# Lipo_Charger_5v.net
KiCad netlist of a schematic drawn in EasyEDA
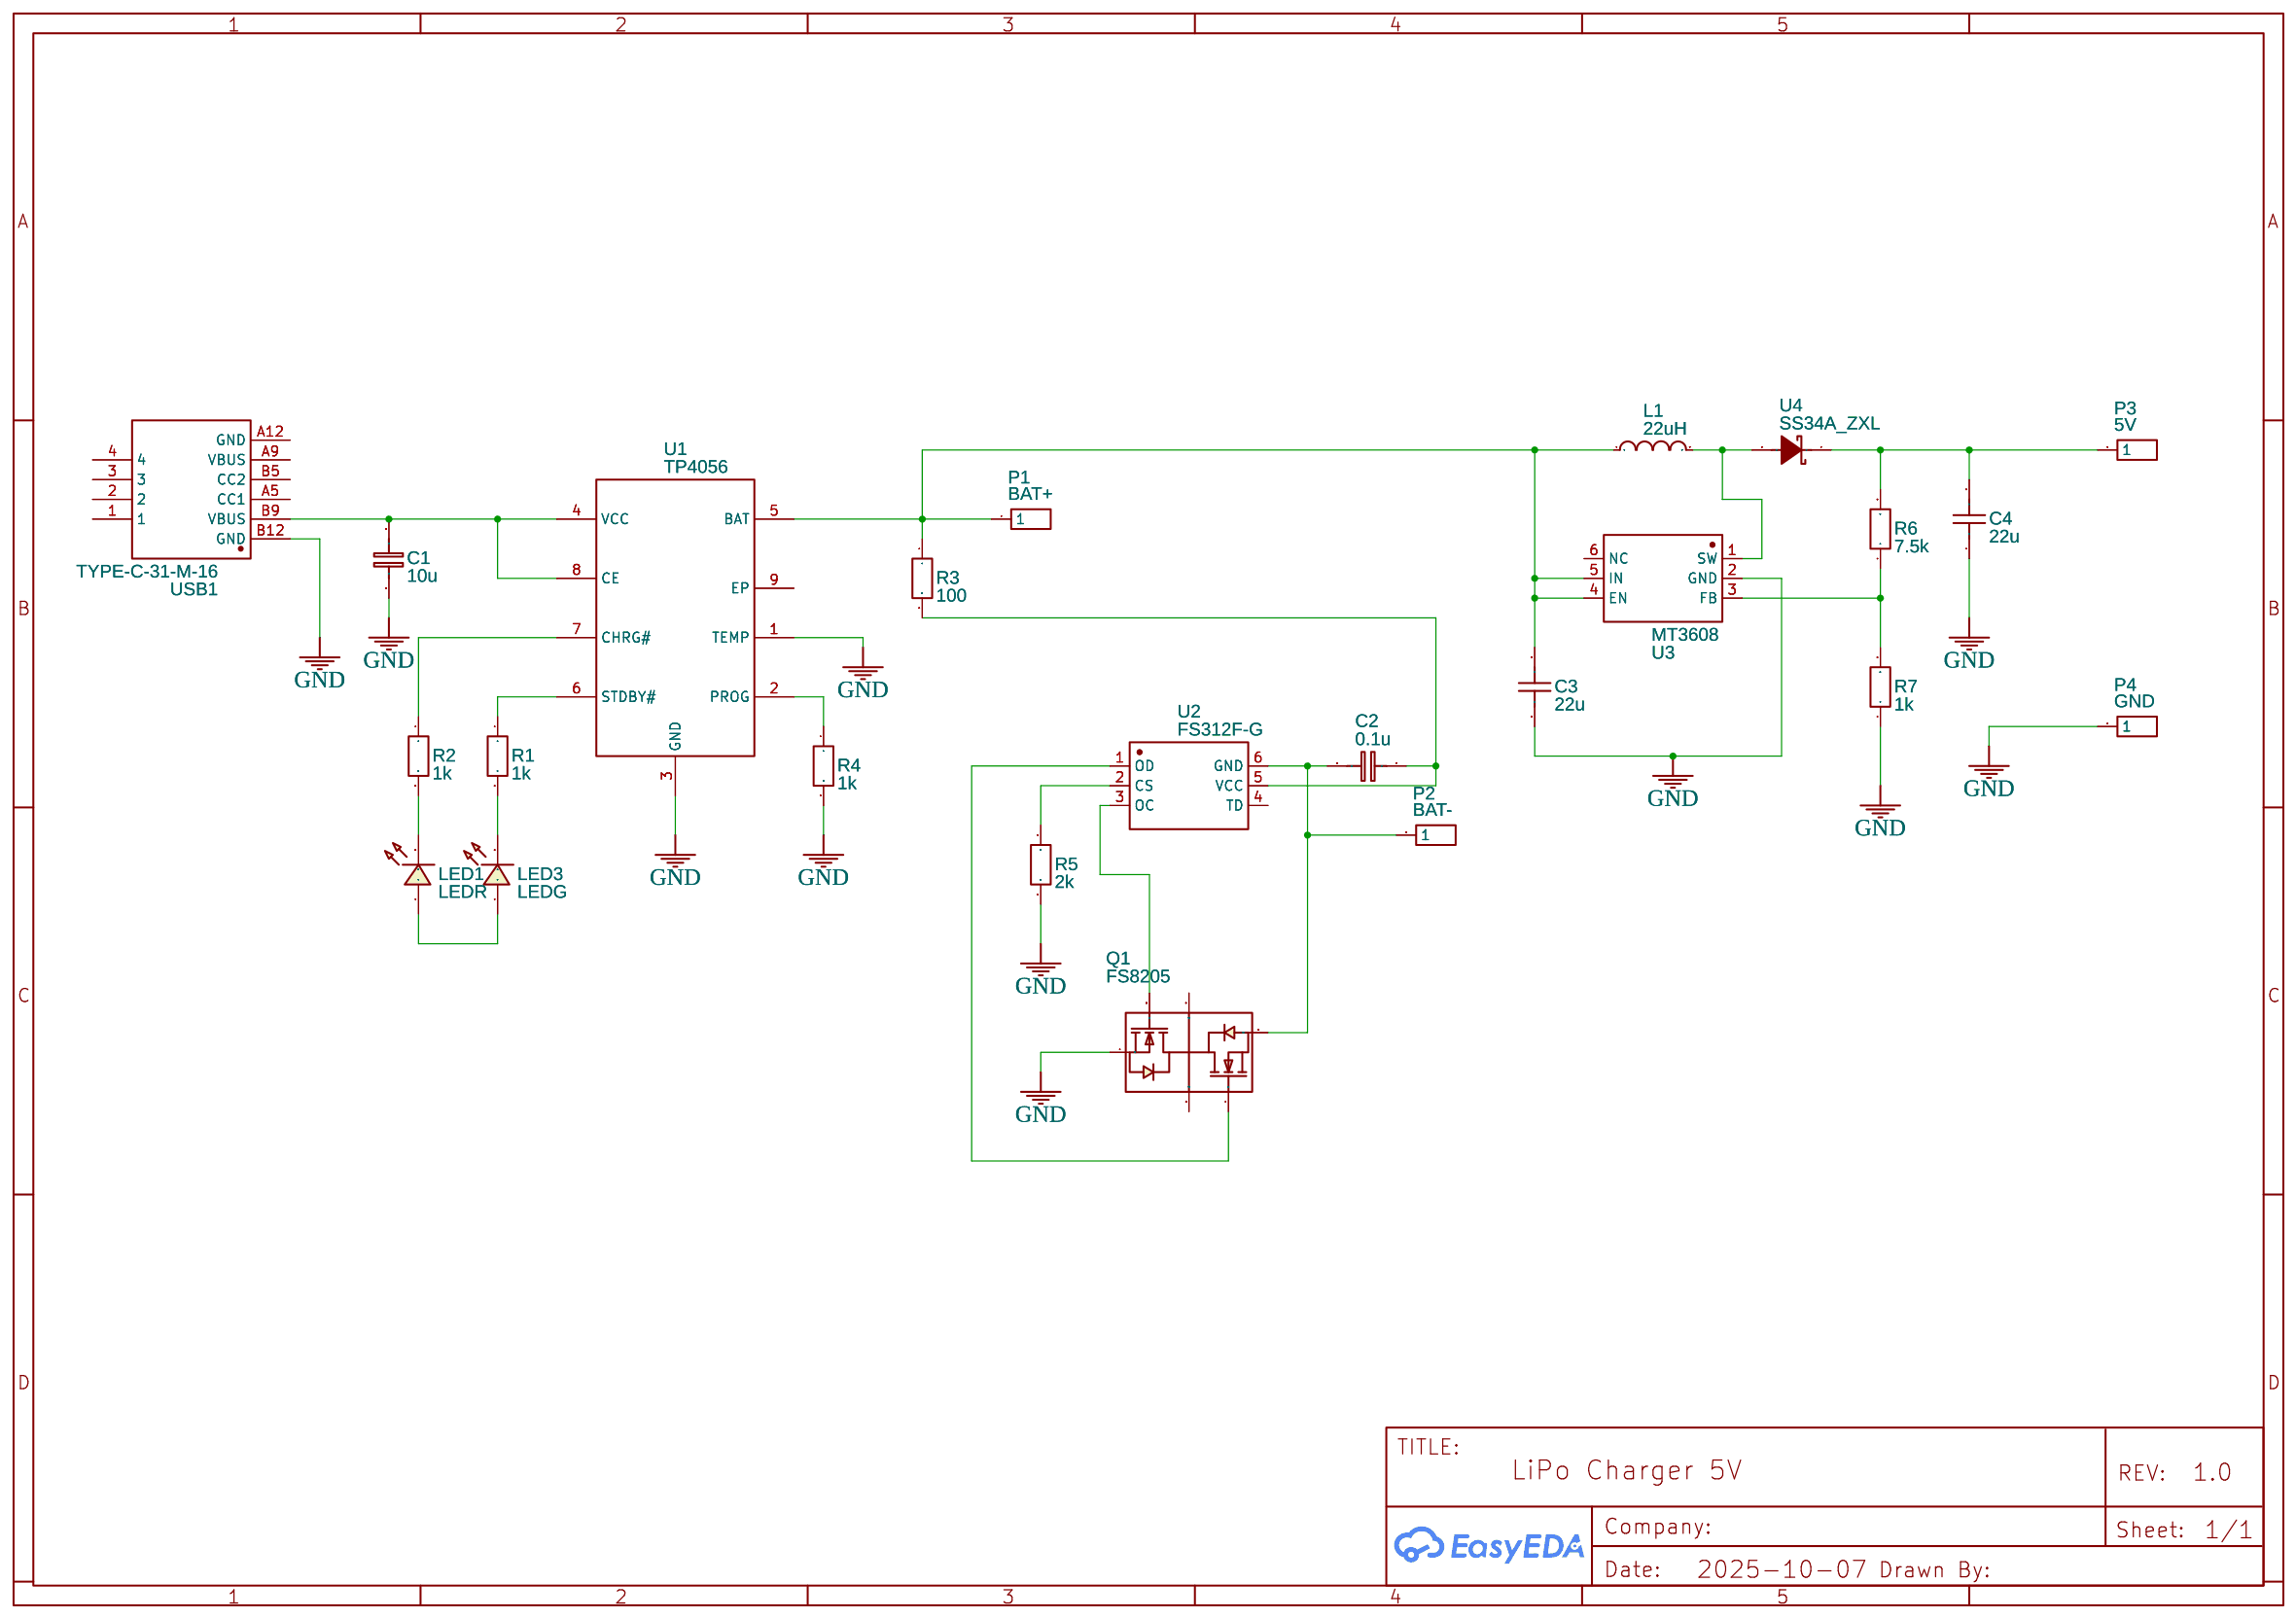
[diagram p0: schematic sheet]

(export (version "E")
  (design (tool "Eeschema 10.0.6"))
  (components
    (comp (ref "C1") (value "10u") (libsource (lib "") (part "C_0603_EU")))
    (comp (ref "C2") (value "0.1u") (libsource (lib "") (part "C_0603_EU_1")))
    (comp (ref "C3") (value "22u") (libsource (lib "") (part "C_0603_US")))
    (comp (ref "C4") (value "22u") (libsource (lib "") (part "C_0603_US")))
    (comp (ref "L1") (value "22uH") (libsource (lib "") (part "L0603_US")))
    (comp (ref "LED1")
      (value "LEDR")
      (fields
        (field (name "Manufacturer Part") "19-217/R6C-AL1M2VY/3T")
        (field (name "Manufacturer") "EVERLIGHT(台湾亿光)")
      )
      (libsource (lib "") (part "LED-0603_R"))
    )
    (comp (ref "LED3")
      (value "LEDG")
      (fields
        (field (name "Manufacturer Part") "19-217/GHC-YR1S2/3T")
        (field (name "Manufacturer") "EVERLIGHT(台湾亿光)")
      )
      (libsource (lib "") (part "LED-0603_G"))
    )
    (comp (ref "P1")
      (value "BAT+")
      (fields (field (name "Manufacturer Part") "2.54-1*1P针") (field (name "Manufacturer") "BOOMELE(博穆精密)"))
      (libsource (lib "") (part "Header-Male-2.54_1x1"))
    )
    (comp (ref "P2")
      (value "BAT-")
      (fields (field (name "Manufacturer Part") "2.54-1*1P针") (field (name "Manufacturer") "BOOMELE(博穆精密)"))
      (libsource (lib "") (part "Header-Male-2.54_1x1"))
    )
    (comp (ref "P3")
      (value "5V")
      (fields (field (name "Manufacturer Part") "2.54-1*1P针") (field (name "Manufacturer") "BOOMELE(博穆精密)"))
      (libsource (lib "") (part "Header-Male-2.54_1x1"))
    )
    (comp (ref "P4")
      (value "GND")
      (fields (field (name "Manufacturer Part") "2.54-1*1P针") (field (name "Manufacturer") "BOOMELE(博穆精密)"))
      (libsource (lib "") (part "Header-Male-2.54_1x1"))
    )
    (comp (ref "Q1")
      (value "FS8205")
      (fields (field (name "Manufacturer") "FORTUNE(富晶)"))
      (libsource (lib "") (part "FS8205"))
    )
    (comp (ref "R1") (value "1k") (libsource (lib "") (part "R_0603_EU")))
    (comp (ref "R2") (value "1k") (libsource (lib "") (part "R_0603_EU")))
    (comp (ref "R3") (value "100") (libsource (lib "") (part "R_0603_EU")))
    (comp (ref "R4") (value "1k") (libsource (lib "") (part "R_0603_EU")))
    (comp (ref "R5") (value "2k") (libsource (lib "") (part "R_0603_EU")))
    (comp (ref "R6") (value "7.5k") (libsource (lib "") (part "R_0603_EU_1")))
    (comp (ref "R7") (value "1k") (libsource (lib "") (part "R_0603_EU_1")))
    (comp (ref "U1")
      (value "TP4056")
      (fields
        (field (name "Manufacturer Part") "TP4056-42-ESOP8")
        (field (name "Manufacturer") "TOPPOWER(南京拓微)")
      )
      (libsource (lib "") (part "TP4056"))
    )
    (comp (ref "U2")
      (value "FS312F-G")
      (fields (field (name "Manufacturer") "FORTUNE(富晶)"))
      (libsource (lib "") (part "FS312F-G"))
    )
    (comp (ref "U3")
      (value "MT3608")
      (fields (field (name "Manufacturer") "西安航天民芯"))
      (libsource (lib "") (part "MT3608"))
    )
    (comp (ref "U4")
      (value "SS34A_ZXL")
      (fields (field (name "Manufacturer Part") "SS34A") (field (name "Manufacturer") "Zhengxin(正芯)"))
      (libsource (lib "") (part "SS34A_ZXL"))
    )
    (comp (ref "USB1")
      (value "TYPE-C-31-M-16")
      (fields (field (name "Manufacturer") "韩国韩荣"))
      (libsource (lib "") (part "TYPE-C-31-M-16"))
    )
  )
  (nets
    (net (code "1") (name "GND") (class "Default")
      (node (ref "C1") (pin "1") (pinfunction "1_1") (pintype "unspecified"))
      (node (ref "C3") (pin "1") (pinfunction "1_1") (pintype "unspecified"))
      (node (ref "C4") (pin "1") (pinfunction "1_1") (pintype "unspecified"))
      (node (ref "P4") (pin "1") (pinfunction "1_1") (pintype "input"))
      (node (ref "Q1") (pin "1") (pinfunction "S1_1") (pintype "unspecified"))
      (node (ref "R4") (pin "2") (pinfunction "2_2") (pintype "unspecified"))
      (node (ref "R5") (pin "2") (pinfunction "2_2") (pintype "unspecified"))
      (node (ref "R7") (pin "1") (pinfunction "1_1") (pintype "unspecified"))
      (node (ref "U1") (pin "1") (pinfunction "TEMP_1") (pintype "unspecified"))
      (node (ref "U1") (pin "3") (pinfunction "GND_3") (pintype "unspecified"))
      (node (ref "U3") (pin "2") (pinfunction "GND_2") (pintype "unspecified"))
      (node (ref "USB1") (pin "B12") (pinfunction "GND_B12") (pintype "unspecified"))
    )
    (net (code "2") (name "Net-(LED1-Pad1)") (class "Default")
      (node (ref "LED1") (pin "1") (pinfunction "1_1") (pintype "unspecified"))
      (node (ref "LED3") (pin "1") (pinfunction "1_1") (pintype "unspecified"))
    )
    (net (code "3") (name "Net-(LED1-Pad2)") (class "Default")
      (node (ref "LED1") (pin "2") (pinfunction "2_2") (pintype "unspecified"))
      (node (ref "R2") (pin "2") (pinfunction "2_2") (pintype "unspecified"))
    )
    (net (code "4") (name "Net-(LED3-Pad2)") (class "Default")
      (node (ref "LED3") (pin "2") (pinfunction "2_2") (pintype "unspecified"))
      (node (ref "R1") (pin "2") (pinfunction "2_2") (pintype "unspecified"))
    )
    (net (code "5") (name "Net-(Q1-G1)") (class "Default")
      (node (ref "Q1") (pin "6") (pinfunction "G1_6") (pintype "unspecified"))
      (node (ref "U2") (pin "3") (pinfunction "OC_3") (pintype "unspecified"))
    )
    (net (code "6") (name "Net-(Q1-G2)") (class "Default")
      (node (ref "Q1") (pin "4") (pinfunction "G2_4") (pintype "unspecified"))
      (node (ref "U2") (pin "1") (pinfunction "OD_1") (pintype "unspecified"))
    )
    (net (code "7") (name "Net-(Q1-S2)") (class "Default")
      (node (ref "C2") (pin "2") (pinfunction "2_2") (pintype "unspecified"))
      (node (ref "P2") (pin "1") (pinfunction "1_1") (pintype "input"))
      (node (ref "Q1") (pin "3") (pinfunction "S2_3") (pintype "unspecified"))
      (node (ref "U2") (pin "6") (pinfunction "GND_6") (pintype "unspecified"))
    )
    (net (code "8") (name "Net-(U1-BAT)") (class "Default")
      (node (ref "C3") (pin "2") (pinfunction "2_2") (pintype "unspecified"))
      (node (ref "L1") (pin "1") (pinfunction "1_1") (pintype "unspecified"))
      (node (ref "P1") (pin "1") (pinfunction "1_1") (pintype "input"))
      (node (ref "R3") (pin "1") (pinfunction "1_1") (pintype "unspecified"))
      (node (ref "U1") (pin "5") (pinfunction "BAT_5") (pintype "unspecified"))
      (node (ref "U3") (pin "4") (pinfunction "EN_4") (pintype "unspecified"))
      (node (ref "U3") (pin "5") (pinfunction "IN_5") (pintype "unspecified"))
    )
    (net (code "9") (name "Net-(U1-CE)") (class "Default")
      (node (ref "C1") (pin "2") (pinfunction "2_2") (pintype "unspecified"))
      (node (ref "U1") (pin "4") (pinfunction "VCC_4") (pintype "unspecified"))
      (node (ref "U1") (pin "8") (pinfunction "CE_8") (pintype "unspecified"))
      (node (ref "USB1") (pin "B9") (pinfunction "VBUS_B9") (pintype "unspecified"))
    )
    (net (code "10") (name "Net-(U1-CHRG#)") (class "Default")
      (node (ref "R2") (pin "1") (pinfunction "1_1") (pintype "unspecified"))
      (node (ref "U1") (pin "7") (pinfunction "CHRG#_7") (pintype "unspecified"))
    )
    (net (code "11") (name "Net-(U1-PROG)") (class "Default")
      (node (ref "R4") (pin "1") (pinfunction "1_1") (pintype "unspecified"))
      (node (ref "U1") (pin "2") (pinfunction "PROG_2") (pintype "unspecified"))
    )
    (net (code "12") (name "Net-(U1-STDBY#)") (class "Default")
      (node (ref "R1") (pin "1") (pinfunction "1_1") (pintype "unspecified"))
      (node (ref "U1") (pin "6") (pinfunction "STDBY#_6") (pintype "unspecified"))
    )
    (net (code "13") (name "Net-(U2-CS)") (class "Default")
      (node (ref "R5") (pin "1") (pinfunction "1_1") (pintype "unspecified"))
      (node (ref "U2") (pin "2") (pinfunction "CS_2") (pintype "unspecified"))
    )
    (net (code "14") (name "Net-(U2-VCC)") (class "Default")
      (node (ref "C2") (pin "1") (pinfunction "1_1") (pintype "unspecified"))
      (node (ref "R3") (pin "2") (pinfunction "2_2") (pintype "unspecified"))
      (node (ref "U2") (pin "5") (pinfunction "VCC_5") (pintype "unspecified"))
    )
    (net (code "15") (name "Net-(U3-FB)") (class "Default")
      (node (ref "R6") (pin "1") (pinfunction "1_1") (pintype "unspecified"))
      (node (ref "R7") (pin "2") (pinfunction "2_2") (pintype "unspecified"))
      (node (ref "U3") (pin "3") (pinfunction "FB_3") (pintype "unspecified"))
    )
    (net (code "16") (name "Net-(U3-SW)") (class "Default")
      (node (ref "L1") (pin "2") (pinfunction "2_2") (pintype "unspecified"))
      (node (ref "U3") (pin "1") (pinfunction "SW_1") (pintype "unspecified"))
      (node (ref "U4") (pin "2") (pinfunction "A_2") (pintype "unspecified"))
    )
    (net (code "17") (name "Net-(U4-K)") (class "Default")
      (node (ref "C4") (pin "2") (pinfunction "2_2") (pintype "unspecified"))
      (node (ref "P3") (pin "1") (pinfunction "1_1") (pintype "input"))
      (node (ref "R6") (pin "2") (pinfunction "2_2") (pintype "unspecified"))
      (node (ref "U4") (pin "1") (pinfunction "K_1") (pintype "unspecified"))
    )
    (net (code "18") (name "unconnected-(Q1-D12-Pad2)") (class "Default")
      (node (ref "Q1") (pin "2") (pinfunction "D12_2") (pintype "unspecified"))
    )
    (net (code "19") (name "unconnected-(Q1-D12-Pad5)") (class "Default")
      (node (ref "Q1") (pin "5") (pinfunction "D12_5") (pintype "unspecified"))
    )
    (net (code "20") (name "unconnected-(U1-EP-Pad9)") (class "Default")
      (node (ref "U1") (pin "9") (pinfunction "EP_9") (pintype "unspecified"))
    )
    (net (code "21") (name "unconnected-(U2-TD-Pad4)") (class "Default")
      (node (ref "U2") (pin "4") (pinfunction "TD_4") (pintype "unspecified"))
    )
    (net (code "22") (name "unconnected-(U3-NC-Pad6)") (class "Default")
      (node (ref "U3") (pin "6") (pinfunction "NC_6") (pintype "unspecified"))
    )
    (net (code "23") (name "unconnected-(USB1-CC1-PadA5)") (class "Default")
      (node (ref "USB1") (pin "A5") (pinfunction "CC1_A5") (pintype "unspecified"))
    )
    (net (code "24") (name "unconnected-(USB1-CC2-PadB5)") (class "Default")
      (node (ref "USB1") (pin "B5") (pinfunction "CC2_B5") (pintype "unspecified"))
    )
    (net (code "25") (name "unconnected-(USB1-GND-PadA12)") (class "Default")
      (node (ref "USB1") (pin "A12") (pinfunction "GND_A12") (pintype "unspecified"))
    )
    (net (code "26") (name "unconnected-(USB1-Pad1)") (class "Default")
      (node (ref "USB1") (pin "1") (pinfunction "1_1") (pintype "unspecified"))
    )
    (net (code "27") (name "unconnected-(USB1-Pad2)") (class "Default")
      (node (ref "USB1") (pin "2") (pinfunction "2_2") (pintype "unspecified"))
    )
    (net (code "28") (name "unconnected-(USB1-Pad3)") (class "Default")
      (node (ref "USB1") (pin "3") (pinfunction "3_3") (pintype "unspecified"))
    )
    (net (code "29") (name "unconnected-(USB1-Pad4)") (class "Default")
      (node (ref "USB1") (pin "4") (pinfunction "4_4") (pintype "unspecified"))
    )
    (net (code "30") (name "unconnected-(USB1-VBUS-PadA9)") (class "Default")
      (node (ref "USB1") (pin "A9") (pinfunction "VBUS_A9") (pintype "unspecified"))
    )
  )
)
